# ServoShield_v2.net
KiCad netlist of a schematic drawn in EAGLE
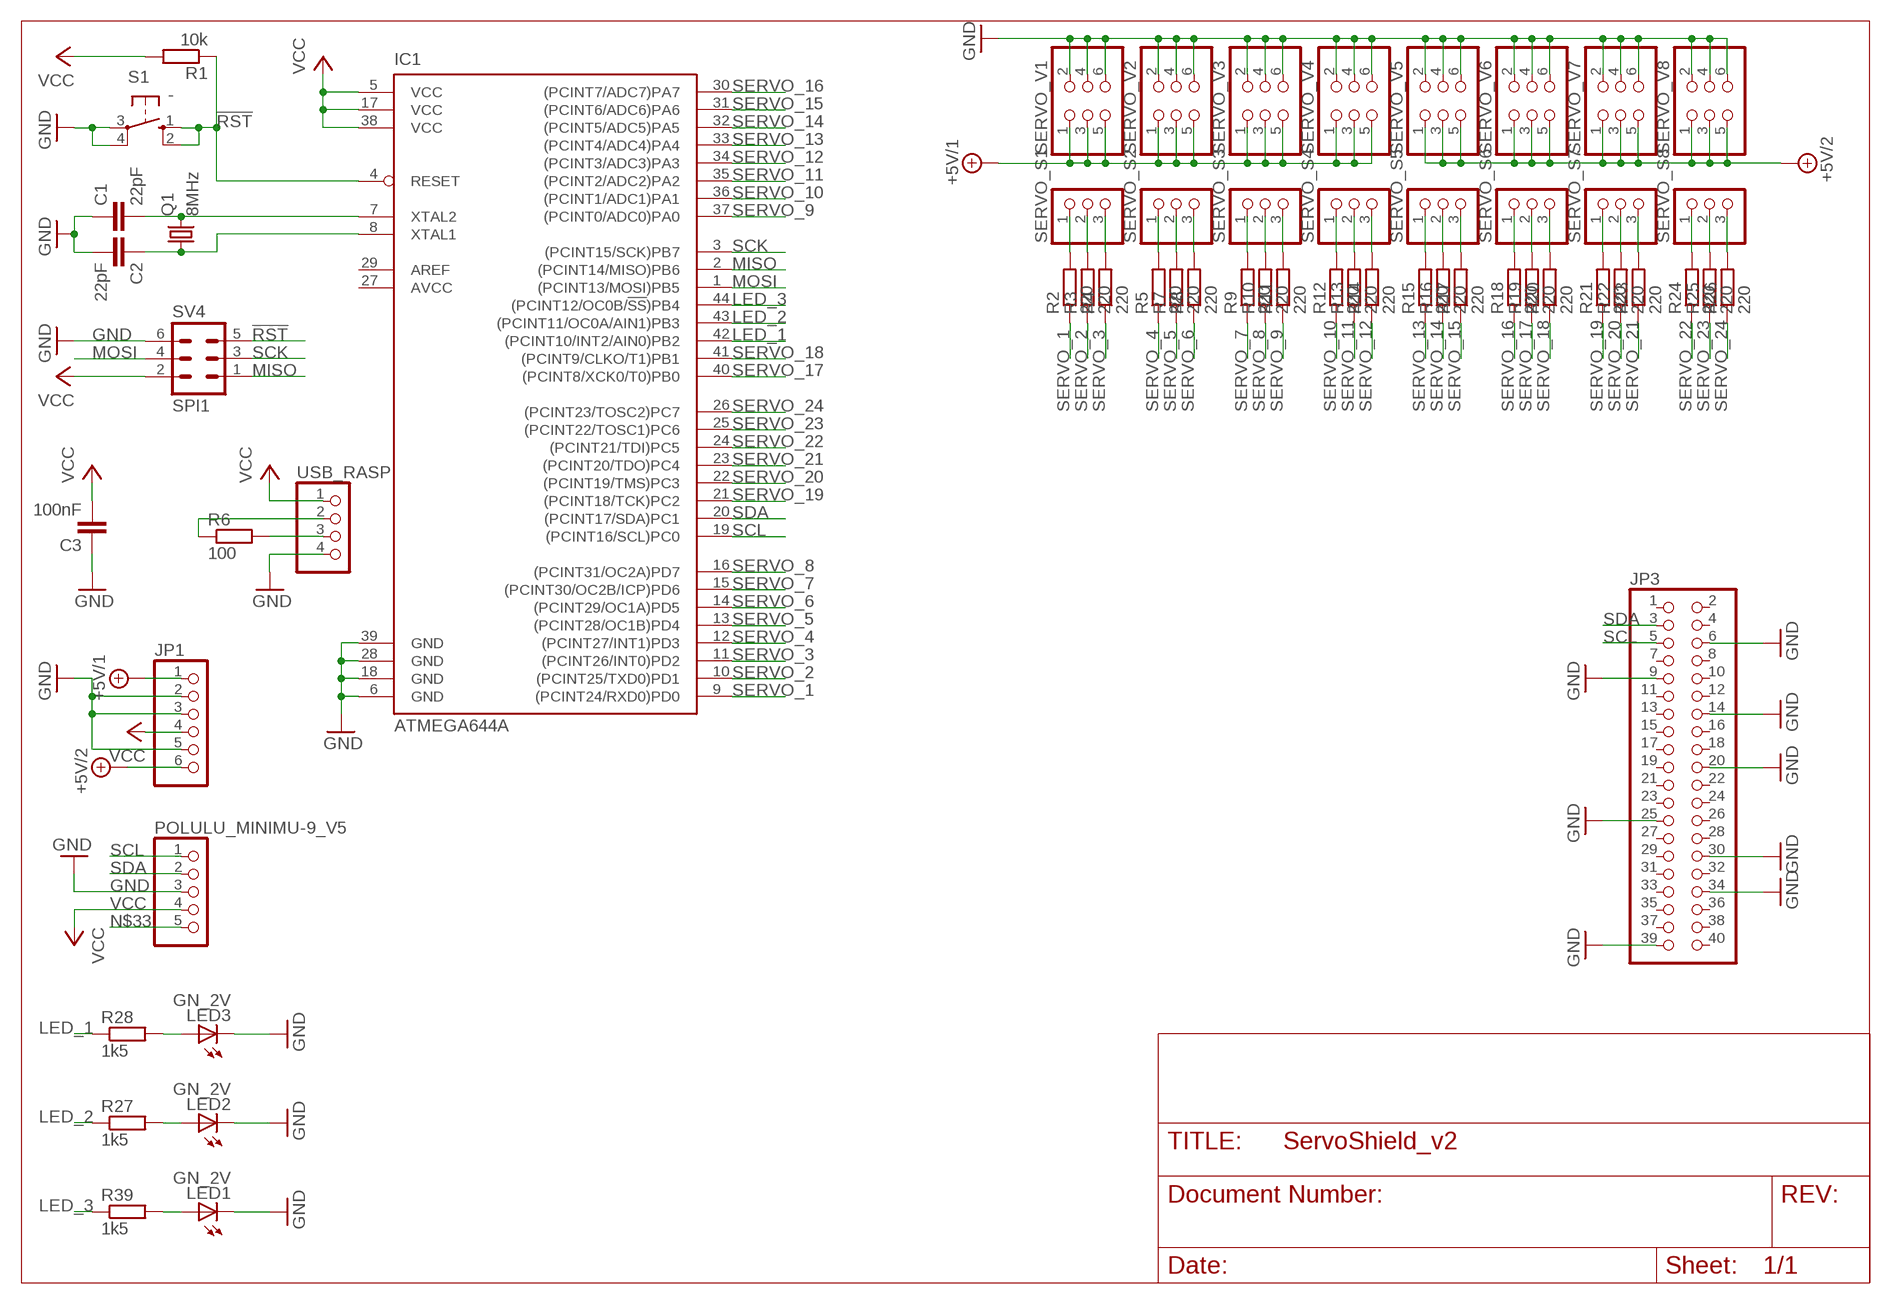
[diagram p0: schematic, sheet 1]

(export (version "E")
  (design (tool "Eeschema 10.0.6"))
  (components
    (comp (ref "C1")
      (value "22pF")
      (footprint "eagle-import:C0805")
      (libsource (lib "eagle-import") (part "C-EUC0805"))
    )
    (comp (ref "C2")
      (value "22pF")
      (footprint "eagle-import:C0805")
      (libsource (lib "eagle-import") (part "C-EUC0805"))
    )
    (comp (ref "C3")
      (value "100nF")
      (footprint "eagle-import:C0805")
      (libsource (lib "eagle-import") (part "resistor_C-EUC0805"))
    )
    (comp (ref "IC1")
      (value "ATMEGA644A")
      (footprint "eagle-import:TQFP44")
      (fields (field (name "MPN") "ATMEGA644PV-10AU"))
      (libsource (lib "eagle-import") (part "ATMEGA644A"))
    )
    (comp (ref "JP1")
      (value "PINHD-1X6")
      (footprint "eagle-import:1X06")
      (libsource (lib "eagle-import") (part "PINHD-1X6"))
    )
    (comp (ref "JP3")
      (value "PINHD-2X20")
      (footprint "eagle-import:2X20")
      (libsource (lib "eagle-import") (part "PINHD-2X20"))
    )
    (comp (ref "LED1")
      (value "GN_2V")
      (footprint "eagle-import:LED3MM")
      (libsource (lib "eagle-import") (part "LED3MM"))
    )
    (comp (ref "LED2")
      (value "GN_2V")
      (footprint "eagle-import:LED3MM")
      (libsource (lib "eagle-import") (part "LED3MM"))
    )
    (comp (ref "LED3")
      (value "GN_2V")
      (footprint "eagle-import:LED3MM")
      (libsource (lib "eagle-import") (part "LED3MM"))
    )
    (comp (ref "POLULU_MINIMU-9_V5")
      (value "PINHD-1X5")
      (footprint "eagle-import:1X05")
      (libsource (lib "eagle-import") (part "PINHD-1X5"))
    )
    (comp (ref "Q1")
      (value "8MHz")
      (footprint "eagle-import:CTS406")
      (libsource (lib "eagle-import") (part "CRYSTALCTS406"))
    )
    (comp (ref "R1")
      (value "10k")
      (footprint "eagle-import:R0805")
      (libsource (lib "eagle-import") (part "resistor_R-EU_R0805"))
    )
    (comp (ref "R2")
      (value "220")
      (footprint "eagle-import:R0805")
      (libsource (lib "eagle-import") (part "resistor_R-EU_R0805"))
    )
    (comp (ref "R3")
      (value "220")
      (footprint "eagle-import:R0805")
      (libsource (lib "eagle-import") (part "resistor_R-EU_R0805"))
    )
    (comp (ref "R4")
      (value "220")
      (footprint "eagle-import:R0805")
      (libsource (lib "eagle-import") (part "resistor_R-EU_R0805"))
    )
    (comp (ref "R5")
      (value "220")
      (footprint "eagle-import:R0805")
      (libsource (lib "eagle-import") (part "resistor_R-EU_R0805"))
    )
    (comp (ref "R6")
      (value "100")
      (footprint "eagle-import:R0805")
      (libsource (lib "eagle-import") (part "R-EU_R0805"))
    )
    (comp (ref "R7")
      (value "220")
      (footprint "eagle-import:R0805")
      (libsource (lib "eagle-import") (part "resistor_R-EU_R0805"))
    )
    (comp (ref "R8")
      (value "220")
      (footprint "eagle-import:R0805")
      (libsource (lib "eagle-import") (part "resistor_R-EU_R0805"))
    )
    (comp (ref "R9")
      (value "220")
      (footprint "eagle-import:R0805")
      (libsource (lib "eagle-import") (part "resistor_R-EU_R0805"))
    )
    (comp (ref "R10")
      (value "220")
      (footprint "eagle-import:R0805")
      (libsource (lib "eagle-import") (part "resistor_R-EU_R0805"))
    )
    (comp (ref "R11")
      (value "220")
      (footprint "eagle-import:R0805")
      (libsource (lib "eagle-import") (part "resistor_R-EU_R0805"))
    )
    (comp (ref "R12")
      (value "220")
      (footprint "eagle-import:R0805")
      (libsource (lib "eagle-import") (part "resistor_R-EU_R0805"))
    )
    (comp (ref "R13")
      (value "220")
      (footprint "eagle-import:R0805")
      (libsource (lib "eagle-import") (part "resistor_R-EU_R0805"))
    )
    (comp (ref "R14")
      (value "220")
      (footprint "eagle-import:R0805")
      (libsource (lib "eagle-import") (part "resistor_R-EU_R0805"))
    )
    (comp (ref "R15")
      (value "220")
      (footprint "eagle-import:R0805")
      (libsource (lib "eagle-import") (part "resistor_R-EU_R0805"))
    )
    (comp (ref "R16")
      (value "220")
      (footprint "eagle-import:R0805")
      (libsource (lib "eagle-import") (part "resistor_R-EU_R0805"))
    )
    (comp (ref "R17")
      (value "220")
      (footprint "eagle-import:R0805")
      (libsource (lib "eagle-import") (part "resistor_R-EU_R0805"))
    )
    (comp (ref "R18")
      (value "220")
      (footprint "eagle-import:R0805")
      (libsource (lib "eagle-import") (part "resistor_R-EU_R0805"))
    )
    (comp (ref "R19")
      (value "220")
      (footprint "eagle-import:R0805")
      (libsource (lib "eagle-import") (part "resistor_R-EU_R0805"))
    )
    (comp (ref "R20")
      (value "220")
      (footprint "eagle-import:R0805")
      (libsource (lib "eagle-import") (part "resistor_R-EU_R0805"))
    )
    (comp (ref "R21")
      (value "220")
      (footprint "eagle-import:R0805")
      (libsource (lib "eagle-import") (part "resistor_R-EU_R0805"))
    )
    (comp (ref "R22")
      (value "220")
      (footprint "eagle-import:R0805")
      (libsource (lib "eagle-import") (part "resistor_R-EU_R0805"))
    )
    (comp (ref "R23")
      (value "220")
      (footprint "eagle-import:R0805")
      (libsource (lib "eagle-import") (part "resistor_R-EU_R0805"))
    )
    (comp (ref "R24")
      (value "220")
      (footprint "eagle-import:R0805")
      (libsource (lib "eagle-import") (part "resistor_R-EU_R0805"))
    )
    (comp (ref "R25")
      (value "220")
      (footprint "eagle-import:R0805")
      (libsource (lib "eagle-import") (part "resistor_R-EU_R0805"))
    )
    (comp (ref "R26")
      (value "220")
      (footprint "eagle-import:R0805")
      (libsource (lib "eagle-import") (part "resistor_R-EU_R0805"))
    )
    (comp (ref "R27")
      (value "1k5")
      (footprint "eagle-import:R0805")
      (libsource (lib "eagle-import") (part "R-EU_R0805"))
    )
    (comp (ref "R28")
      (value "1k5")
      (footprint "eagle-import:R0805")
      (libsource (lib "eagle-import") (part "R-EU_R0805"))
    )
    (comp (ref "R39")
      (value "1k5")
      (footprint "eagle-import:R0805")
      (libsource (lib "eagle-import") (part "R-EU_R0805"))
    )
    (comp (ref "S1")
      (value "-")
      (footprint "eagle-import:B3F-10XX")
      (fields (field (name "MPN") "B3F-1000"))
      (libsource (lib "eagle-import") (part "10-XX"))
    )
    (comp (ref "SERVO_S1")
      (value "PINHD-1X3")
      (footprint "eagle-import:1X03")
      (libsource (lib "eagle-import") (part "PINHD-1X3"))
    )
    (comp (ref "SERVO_S2")
      (value "PINHD-1X3")
      (footprint "eagle-import:1X03")
      (libsource (lib "eagle-import") (part "PINHD-1X3"))
    )
    (comp (ref "SERVO_S3")
      (value "PINHD-1X3")
      (footprint "eagle-import:1X03")
      (libsource (lib "eagle-import") (part "PINHD-1X3"))
    )
    (comp (ref "SERVO_S4")
      (value "PINHD-1X3")
      (footprint "eagle-import:1X03")
      (libsource (lib "eagle-import") (part "PINHD-1X3"))
    )
    (comp (ref "SERVO_S5")
      (value "PINHD-1X3")
      (footprint "eagle-import:1X03")
      (libsource (lib "eagle-import") (part "PINHD-1X3"))
    )
    (comp (ref "SERVO_S6")
      (value "PINHD-1X3")
      (footprint "eagle-import:1X03")
      (libsource (lib "eagle-import") (part "PINHD-1X3"))
    )
    (comp (ref "SERVO_S7")
      (value "PINHD-1X3")
      (footprint "eagle-import:1X03")
      (libsource (lib "eagle-import") (part "PINHD-1X3"))
    )
    (comp (ref "SERVO_S8")
      (value "PINHD-1X3")
      (footprint "eagle-import:1X03")
      (libsource (lib "eagle-import") (part "PINHD-1X3"))
    )
    (comp (ref "SERVO_V1")
      (value "PINHD-2X3")
      (footprint "eagle-import:2X03")
      (libsource (lib "eagle-import") (part "PINHD-2X3"))
    )
    (comp (ref "SERVO_V2")
      (value "PINHD-2X3")
      (footprint "eagle-import:2X03")
      (libsource (lib "eagle-import") (part "PINHD-2X3"))
    )
    (comp (ref "SERVO_V3")
      (value "PINHD-2X3")
      (footprint "eagle-import:2X03")
      (libsource (lib "eagle-import") (part "PINHD-2X3"))
    )
    (comp (ref "SERVO_V4")
      (value "PINHD-2X3")
      (footprint "eagle-import:2X03")
      (libsource (lib "eagle-import") (part "PINHD-2X3"))
    )
    (comp (ref "SERVO_V5")
      (value "PINHD-2X3")
      (footprint "eagle-import:2X03")
      (libsource (lib "eagle-import") (part "PINHD-2X3"))
    )
    (comp (ref "SERVO_V6")
      (value "PINHD-2X3")
      (footprint "eagle-import:2X03")
      (libsource (lib "eagle-import") (part "PINHD-2X3"))
    )
    (comp (ref "SERVO_V7")
      (value "PINHD-2X3")
      (footprint "eagle-import:2X03")
      (libsource (lib "eagle-import") (part "PINHD-2X3"))
    )
    (comp (ref "SERVO_V8")
      (value "PINHD-2X3")
      (footprint "eagle-import:2X03")
      (libsource (lib "eagle-import") (part "PINHD-2X3"))
    )
    (comp (ref "SV4")
      (value "SPI1")
      (footprint "eagle-import:ML6")
      (libsource (lib "eagle-import") (part "ML6"))
    )
    (comp (ref "USB_RASP")
      (value "PINHD-1X4")
      (footprint "eagle-import:1X04")
      (libsource (lib "eagle-import") (part "PINHD-1X4"))
    )
  )
  (nets
    (net (code "1") (name "+5V{slash}1") (class "Default")
      (node (ref "JP1") (pin "1") (pinfunction "1_1") (pintype "passive"))
      (node (ref "SERVO_V1") (pin "1") (pinfunction "1_1") (pintype "passive"))
      (node (ref "SERVO_V1") (pin "3") (pinfunction "3_3") (pintype "passive"))
      (node (ref "SERVO_V1") (pin "5") (pinfunction "5_5") (pintype "passive"))
      (node (ref "SERVO_V2") (pin "1") (pinfunction "1_1") (pintype "passive"))
      (node (ref "SERVO_V2") (pin "3") (pinfunction "3_3") (pintype "passive"))
      (node (ref "SERVO_V2") (pin "5") (pinfunction "5_5") (pintype "passive"))
      (node (ref "SERVO_V3") (pin "1") (pinfunction "1_1") (pintype "passive"))
      (node (ref "SERVO_V3") (pin "3") (pinfunction "3_3") (pintype "passive"))
      (node (ref "SERVO_V3") (pin "5") (pinfunction "5_5") (pintype "passive"))
      (node (ref "SERVO_V4") (pin "1") (pinfunction "1_1") (pintype "passive"))
      (node (ref "SERVO_V4") (pin "3") (pinfunction "3_3") (pintype "passive"))
      (node (ref "SERVO_V4") (pin "5") (pinfunction "5_5") (pintype "passive"))
    )
    (net (code "2") (name "+5V{slash}2") (class "Default")
      (node (ref "JP1") (pin "6") (pinfunction "6_6") (pintype "passive"))
      (node (ref "SERVO_V5") (pin "1") (pinfunction "1_1") (pintype "passive"))
      (node (ref "SERVO_V5") (pin "3") (pinfunction "3_3") (pintype "passive"))
      (node (ref "SERVO_V5") (pin "5") (pinfunction "5_5") (pintype "passive"))
      (node (ref "SERVO_V6") (pin "1") (pinfunction "1_1") (pintype "passive"))
      (node (ref "SERVO_V6") (pin "3") (pinfunction "3_3") (pintype "passive"))
      (node (ref "SERVO_V6") (pin "5") (pinfunction "5_5") (pintype "passive"))
      (node (ref "SERVO_V7") (pin "1") (pinfunction "1_1") (pintype "passive"))
      (node (ref "SERVO_V7") (pin "3") (pinfunction "3_3") (pintype "passive"))
      (node (ref "SERVO_V7") (pin "5") (pinfunction "5_5") (pintype "passive"))
      (node (ref "SERVO_V8") (pin "1") (pinfunction "1_1") (pintype "passive"))
      (node (ref "SERVO_V8") (pin "3") (pinfunction "3_3") (pintype "passive"))
      (node (ref "SERVO_V8") (pin "5") (pinfunction "5_5") (pintype "passive"))
    )
    (net (code "3") (name "/AVCC") (class "Default")
      (node (ref "IC1") (pin "27") (pinfunction "AVCC_27") (pintype "power_in"))
    )
    (net (code "4") (name "/LED_1") (class "Default")
      (node (ref "IC1") (pin "42") (pinfunction "(PCINT10/INT2/AIN0)PB2_42") (pintype "bidirectional"))
      (node (ref "R28") (pin "1") (pinfunction "1_1") (pintype "passive"))
    )
    (net (code "5") (name "/LED_2") (class "Default")
      (node (ref "IC1") (pin "43") (pinfunction "(PCINT11/OC0A/AIN1)PB3_43") (pintype "bidirectional"))
      (node (ref "R27") (pin "1") (pinfunction "1_1") (pintype "passive"))
    )
    (net (code "6") (name "/LED_3") (class "Default")
      (node (ref "IC1") (pin "44") (pinfunction "(PCINT12/OC0B/~{SS})PB4_44") (pintype "bidirectional"))
      (node (ref "R39") (pin "1") (pinfunction "1_1") (pintype "passive"))
    )
    (net (code "7") (name "/MISO") (class "Default")
      (node (ref "IC1") (pin "2") (pinfunction "(PCINT14/MISO)PB6_2") (pintype "bidirectional"))
      (node (ref "SV4") (pin "1") (pinfunction "1_1") (pintype "passive"))
    )
    (net (code "8") (name "/MOSI") (class "Default")
      (node (ref "IC1") (pin "1") (pinfunction "(PCINT13/MOSI)PB5_1") (pintype "bidirectional"))
      (node (ref "SV4") (pin "4") (pinfunction "4_4") (pintype "passive"))
    )
    (net (code "9") (name "/N$33") (class "Default")
      (node (ref "POLULU_MINIMU-9_V5") (pin "5") (pinfunction "5_5") (pintype "passive"))
    )
    (net (code "10") (name "/SCK") (class "Default")
      (node (ref "IC1") (pin "3") (pinfunction "(PCINT15/SCK)PB7_3") (pintype "bidirectional"))
      (node (ref "SV4") (pin "3") (pinfunction "3_3") (pintype "passive"))
    )
    (net (code "11") (name "/SCL") (class "Default")
      (node (ref "IC1") (pin "19") (pinfunction "(PCINT16/SCL)PC0_19") (pintype "output"))
      (node (ref "JP3") (pin "5") (pinfunction "5_5") (pintype "passive"))
      (node (ref "POLULU_MINIMU-9_V5") (pin "1") (pinfunction "1_1") (pintype "passive"))
    )
    (net (code "12") (name "/SDA") (class "Default")
      (node (ref "IC1") (pin "20") (pinfunction "(PCINT17/SDA)PC1_20") (pintype "output"))
      (node (ref "JP3") (pin "3") (pinfunction "3_3") (pintype "passive"))
      (node (ref "POLULU_MINIMU-9_V5") (pin "2") (pinfunction "2_2") (pintype "passive"))
    )
    (net (code "13") (name "/SERVO_1") (class "Default")
      (node (ref "IC1") (pin "9") (pinfunction "(PCINT24/RXD0)PD0_9") (pintype "bidirectional"))
      (node (ref "R2") (pin "1") (pinfunction "1_1") (pintype "passive"))
    )
    (net (code "14") (name "/SERVO_2") (class "Default")
      (node (ref "IC1") (pin "10") (pinfunction "(PCINT25/TXD0)PD1_10") (pintype "bidirectional"))
      (node (ref "R3") (pin "1") (pinfunction "1_1") (pintype "passive"))
    )
    (net (code "15") (name "/SERVO_3") (class "Default")
      (node (ref "IC1") (pin "11") (pinfunction "(PCINT26/INT0)PD2_11") (pintype "bidirectional"))
      (node (ref "R4") (pin "1") (pinfunction "1_1") (pintype "passive"))
    )
    (net (code "16") (name "/SERVO_4") (class "Default")
      (node (ref "IC1") (pin "12") (pinfunction "(PCINT27/INT1)PD3_12") (pintype "bidirectional"))
      (node (ref "R5") (pin "1") (pinfunction "1_1") (pintype "passive"))
    )
    (net (code "17") (name "/SERVO_5") (class "Default")
      (node (ref "IC1") (pin "13") (pinfunction "(PCINT28/OC1B)PD4_13") (pintype "bidirectional"))
      (node (ref "R7") (pin "1") (pinfunction "1_1") (pintype "passive"))
    )
    (net (code "18") (name "/SERVO_6") (class "Default")
      (node (ref "IC1") (pin "14") (pinfunction "(PCINT29/OC1A)PD5_14") (pintype "bidirectional"))
      (node (ref "R8") (pin "1") (pinfunction "1_1") (pintype "passive"))
    )
    (net (code "19") (name "/SERVO_7") (class "Default")
      (node (ref "IC1") (pin "15") (pinfunction "(PCINT30/OC2B/ICP)PD6_15") (pintype "bidirectional"))
      (node (ref "R9") (pin "1") (pinfunction "1_1") (pintype "passive"))
    )
    (net (code "20") (name "/SERVO_8") (class "Default")
      (node (ref "IC1") (pin "16") (pinfunction "(PCINT31/OC2A)PD7_16") (pintype "bidirectional"))
      (node (ref "R10") (pin "1") (pinfunction "1_1") (pintype "passive"))
    )
    (net (code "21") (name "/SERVO_9") (class "Default")
      (node (ref "IC1") (pin "37") (pinfunction "(PCINT0/ADC0)PA0_37") (pintype "bidirectional"))
      (node (ref "R11") (pin "1") (pinfunction "1_1") (pintype "passive"))
    )
    (net (code "22") (name "/SERVO_10") (class "Default")
      (node (ref "IC1") (pin "36") (pinfunction "(PCINT1/ADC1)PA1_36") (pintype "bidirectional"))
      (node (ref "R12") (pin "1") (pinfunction "1_1") (pintype "passive"))
    )
    (net (code "23") (name "/SERVO_11") (class "Default")
      (node (ref "IC1") (pin "35") (pinfunction "(PCINT2/ADC2)PA2_35") (pintype "bidirectional"))
      (node (ref "R13") (pin "1") (pinfunction "1_1") (pintype "passive"))
    )
    (net (code "24") (name "/SERVO_12") (class "Default")
      (node (ref "IC1") (pin "34") (pinfunction "(PCINT3/ADC3)PA3_34") (pintype "bidirectional"))
      (node (ref "R14") (pin "1") (pinfunction "1_1") (pintype "passive"))
    )
    (net (code "25") (name "/SERVO_13") (class "Default")
      (node (ref "IC1") (pin "33") (pinfunction "(PCINT4/ADC4)PA4_33") (pintype "bidirectional"))
      (node (ref "R15") (pin "1") (pinfunction "1_1") (pintype "passive"))
    )
    (net (code "26") (name "/SERVO_14") (class "Default")
      (node (ref "IC1") (pin "32") (pinfunction "(PCINT5/ADC5)PA5_32") (pintype "bidirectional"))
      (node (ref "R16") (pin "1") (pinfunction "1_1") (pintype "passive"))
    )
    (net (code "27") (name "/SERVO_15") (class "Default")
      (node (ref "IC1") (pin "31") (pinfunction "(PCINT6/ADC6)PA6_31") (pintype "bidirectional"))
      (node (ref "R17") (pin "1") (pinfunction "1_1") (pintype "passive"))
    )
    (net (code "28") (name "/SERVO_16") (class "Default")
      (node (ref "IC1") (pin "30") (pinfunction "(PCINT7/ADC7)PA7_30") (pintype "bidirectional"))
      (node (ref "R18") (pin "1") (pinfunction "1_1") (pintype "passive"))
    )
    (net (code "29") (name "/SERVO_17") (class "Default")
      (node (ref "IC1") (pin "40") (pinfunction "(PCINT8/XCK0/T0)PB0_40") (pintype "bidirectional"))
      (node (ref "R19") (pin "1") (pinfunction "1_1") (pintype "passive"))
    )
    (net (code "30") (name "/SERVO_18") (class "Default")
      (node (ref "IC1") (pin "41") (pinfunction "(PCINT9/CLKO/T1)PB1_41") (pintype "bidirectional"))
      (node (ref "R20") (pin "1") (pinfunction "1_1") (pintype "passive"))
    )
    (net (code "31") (name "/SERVO_19") (class "Default")
      (node (ref "IC1") (pin "21") (pinfunction "(PCINT18/TCK)PC2_21") (pintype "output"))
      (node (ref "R21") (pin "1") (pinfunction "1_1") (pintype "passive"))
    )
    (net (code "32") (name "/SERVO_20") (class "Default")
      (node (ref "IC1") (pin "22") (pinfunction "(PCINT19/TMS)PC3_22") (pintype "output"))
      (node (ref "R22") (pin "1") (pinfunction "1_1") (pintype "passive"))
    )
    (net (code "33") (name "/SERVO_21") (class "Default")
      (node (ref "IC1") (pin "23") (pinfunction "(PCINT20/TDO)PC4_23") (pintype "output"))
      (node (ref "R23") (pin "1") (pinfunction "1_1") (pintype "passive"))
    )
    (net (code "34") (name "/SERVO_22") (class "Default")
      (node (ref "IC1") (pin "24") (pinfunction "(PCINT21/TDI)PC5_24") (pintype "output"))
      (node (ref "R24") (pin "1") (pinfunction "1_1") (pintype "passive"))
    )
    (net (code "35") (name "/SERVO_23") (class "Default")
      (node (ref "IC1") (pin "25") (pinfunction "(PCINT22/TOSC1)PC6_25") (pintype "output"))
      (node (ref "R25") (pin "1") (pinfunction "1_1") (pintype "passive"))
    )
    (net (code "36") (name "/SERVO_24") (class "Default")
      (node (ref "IC1") (pin "26") (pinfunction "(PCINT23/TOSC2)PC7_26") (pintype "output"))
      (node (ref "R26") (pin "1") (pinfunction "1_1") (pintype "passive"))
    )
    (net (code "37") (name "/~{RST}") (class "Default")
      (node (ref "IC1") (pin "4") (pinfunction "RESET_4") (pintype "input"))
      (node (ref "R1") (pin "1") (pinfunction "1_1") (pintype "passive"))
      (node (ref "S1") (pin "1") (pinfunction "S_1") (pintype "passive"))
      (node (ref "S1") (pin "2") (pinfunction "S1_2") (pintype "passive"))
      (node (ref "SV4") (pin "5") (pinfunction "5_5") (pintype "passive"))
    )
    (net (code "38") (name "GND") (class "Default")
      (node (ref "C1") (pin "1") (pinfunction "1_1") (pintype "passive"))
      (node (ref "C2") (pin "2") (pinfunction "2_2") (pintype "passive"))
      (node (ref "C3") (pin "1") (pinfunction "1_1") (pintype "passive"))
      (node (ref "IC1") (pin "18") (pinfunction "GND_18") (pintype "power_in"))
      (node (ref "IC1") (pin "28") (pinfunction "GND_28") (pintype "power_in"))
      (node (ref "IC1") (pin "39") (pinfunction "GND_39") (pintype "power_in"))
      (node (ref "IC1") (pin "6") (pinfunction "GND_6") (pintype "power_in"))
      (node (ref "JP1") (pin "2") (pinfunction "2_2") (pintype "passive"))
      (node (ref "JP1") (pin "3") (pinfunction "3_3") (pintype "passive"))
      (node (ref "JP1") (pin "5") (pinfunction "5_5") (pintype "passive"))
      (node (ref "JP3") (pin "14") (pinfunction "14_14") (pintype "passive"))
      (node (ref "JP3") (pin "20") (pinfunction "20_20") (pintype "passive"))
      (node (ref "JP3") (pin "25") (pinfunction "25_25") (pintype "passive"))
      (node (ref "JP3") (pin "30") (pinfunction "30_30") (pintype "passive"))
      (node (ref "JP3") (pin "34") (pinfunction "34_34") (pintype "passive"))
      (node (ref "JP3") (pin "39") (pinfunction "39_39") (pintype "passive"))
      (node (ref "JP3") (pin "6") (pinfunction "6_6") (pintype "passive"))
      (node (ref "JP3") (pin "9") (pinfunction "9_9") (pintype "passive"))
      (node (ref "LED1") (pin "K") (pinfunction "C_K") (pintype "passive"))
      (node (ref "LED2") (pin "K") (pinfunction "C_K") (pintype "passive"))
      (node (ref "LED3") (pin "K") (pinfunction "C_K") (pintype "passive"))
      (node (ref "POLULU_MINIMU-9_V5") (pin "3") (pinfunction "3_3") (pintype "passive"))
      (node (ref "S1") (pin "3") (pinfunction "P_3") (pintype "passive"))
      (node (ref "S1") (pin "4") (pinfunction "P1_4") (pintype "passive"))
      (node (ref "SERVO_V1") (pin "2") (pinfunction "2_2") (pintype "passive"))
      (node (ref "SERVO_V1") (pin "4") (pinfunction "4_4") (pintype "passive"))
      (node (ref "SERVO_V1") (pin "6") (pinfunction "6_6") (pintype "passive"))
      (node (ref "SERVO_V2") (pin "2") (pinfunction "2_2") (pintype "passive"))
      (node (ref "SERVO_V2") (pin "4") (pinfunction "4_4") (pintype "passive"))
      (node (ref "SERVO_V2") (pin "6") (pinfunction "6_6") (pintype "passive"))
      (node (ref "SERVO_V3") (pin "2") (pinfunction "2_2") (pintype "passive"))
      (node (ref "SERVO_V3") (pin "4") (pinfunction "4_4") (pintype "passive"))
      (node (ref "SERVO_V3") (pin "6") (pinfunction "6_6") (pintype "passive"))
      (node (ref "SERVO_V4") (pin "2") (pinfunction "2_2") (pintype "passive"))
      (node (ref "SERVO_V4") (pin "4") (pinfunction "4_4") (pintype "passive"))
      (node (ref "SERVO_V4") (pin "6") (pinfunction "6_6") (pintype "passive"))
      (node (ref "SERVO_V5") (pin "2") (pinfunction "2_2") (pintype "passive"))
      (node (ref "SERVO_V5") (pin "4") (pinfunction "4_4") (pintype "passive"))
      (node (ref "SERVO_V5") (pin "6") (pinfunction "6_6") (pintype "passive"))
      (node (ref "SERVO_V6") (pin "2") (pinfunction "2_2") (pintype "passive"))
      (node (ref "SERVO_V6") (pin "4") (pinfunction "4_4") (pintype "passive"))
      (node (ref "SERVO_V6") (pin "6") (pinfunction "6_6") (pintype "passive"))
      (node (ref "SERVO_V7") (pin "2") (pinfunction "2_2") (pintype "passive"))
      (node (ref "SERVO_V7") (pin "4") (pinfunction "4_4") (pintype "passive"))
      (node (ref "SERVO_V7") (pin "6") (pinfunction "6_6") (pintype "passive"))
      (node (ref "SERVO_V8") (pin "2") (pinfunction "2_2") (pintype "passive"))
      (node (ref "SERVO_V8") (pin "4") (pinfunction "4_4") (pintype "passive"))
      (node (ref "SERVO_V8") (pin "6") (pinfunction "6_6") (pintype "passive"))
      (node (ref "SV4") (pin "6") (pinfunction "6_6") (pintype "passive"))
      (node (ref "USB_RASP") (pin "4") (pinfunction "4_4") (pintype "passive"))
    )
    (net (code "39") (name "Net-(IC1-XTAL1)") (class "Default")
      (node (ref "C2") (pin "1") (pinfunction "1_1") (pintype "passive"))
      (node (ref "IC1") (pin "8") (pinfunction "XTAL1_8") (pintype "bidirectional"))
      (node (ref "Q1") (pin "1") (pinfunction "1_1") (pintype "passive"))
    )
    (net (code "40") (name "Net-(IC1-XTAL2)") (class "Default")
      (node (ref "C1") (pin "2") (pinfunction "2_2") (pintype "passive"))
      (node (ref "IC1") (pin "7") (pinfunction "XTAL2_7") (pintype "bidirectional"))
      (node (ref "Q1") (pin "3") (pinfunction "2_3") (pintype "passive"))
    )
    (net (code "41") (name "Net-(LED1-PadA)") (class "Default")
      (node (ref "LED1") (pin "A") (pinfunction "A_A") (pintype "passive"))
      (node (ref "R39") (pin "2") (pinfunction "2_2") (pintype "passive"))
    )
    (net (code "42") (name "Net-(LED2-PadA)") (class "Default")
      (node (ref "LED2") (pin "A") (pinfunction "A_A") (pintype "passive"))
      (node (ref "R27") (pin "2") (pinfunction "2_2") (pintype "passive"))
    )
    (net (code "43") (name "Net-(LED3-PadA)") (class "Default")
      (node (ref "LED3") (pin "A") (pinfunction "A_A") (pintype "passive"))
      (node (ref "R28") (pin "2") (pinfunction "2_2") (pintype "passive"))
    )
    (net (code "44") (name "Net-(R2-Pad2)") (class "Default")
      (node (ref "R2") (pin "2") (pinfunction "2_2") (pintype "passive"))
      (node (ref "SERVO_S1") (pin "1") (pinfunction "1_1") (pintype "passive"))
    )
    (net (code "45") (name "Net-(R3-Pad2)") (class "Default")
      (node (ref "R3") (pin "2") (pinfunction "2_2") (pintype "passive"))
      (node (ref "SERVO_S1") (pin "2") (pinfunction "2_2") (pintype "passive"))
    )
    (net (code "46") (name "Net-(R4-Pad2)") (class "Default")
      (node (ref "R4") (pin "2") (pinfunction "2_2") (pintype "passive"))
      (node (ref "SERVO_S1") (pin "3") (pinfunction "3_3") (pintype "passive"))
    )
    (net (code "47") (name "Net-(R5-Pad2)") (class "Default")
      (node (ref "R5") (pin "2") (pinfunction "2_2") (pintype "passive"))
      (node (ref "SERVO_S2") (pin "1") (pinfunction "1_1") (pintype "passive"))
    )
    (net (code "48") (name "Net-(R6-Pad1)") (class "Default")
      (node (ref "R6") (pin "1") (pinfunction "1_1") (pintype "passive"))
      (node (ref "USB_RASP") (pin "2") (pinfunction "2_2") (pintype "passive"))
    )
    (net (code "49") (name "Net-(R6-Pad2)") (class "Default")
      (node (ref "R6") (pin "2") (pinfunction "2_2") (pintype "passive"))
      (node (ref "USB_RASP") (pin "3") (pinfunction "3_3") (pintype "passive"))
    )
    (net (code "50") (name "Net-(R7-Pad2)") (class "Default")
      (node (ref "R7") (pin "2") (pinfunction "2_2") (pintype "passive"))
      (node (ref "SERVO_S2") (pin "2") (pinfunction "2_2") (pintype "passive"))
    )
    (net (code "51") (name "Net-(R8-Pad2)") (class "Default")
      (node (ref "R8") (pin "2") (pinfunction "2_2") (pintype "passive"))
      (node (ref "SERVO_S2") (pin "3") (pinfunction "3_3") (pintype "passive"))
    )
    (net (code "52") (name "Net-(R9-Pad2)") (class "Default")
      (node (ref "R9") (pin "2") (pinfunction "2_2") (pintype "passive"))
      (node (ref "SERVO_S3") (pin "1") (pinfunction "1_1") (pintype "passive"))
    )
    (net (code "53") (name "Net-(R10-Pad2)") (class "Default")
      (node (ref "R10") (pin "2") (pinfunction "2_2") (pintype "passive"))
      (node (ref "SERVO_S3") (pin "2") (pinfunction "2_2") (pintype "passive"))
    )
    (net (code "54") (name "Net-(R11-Pad2)") (class "Default")
      (node (ref "R11") (pin "2") (pinfunction "2_2") (pintype "passive"))
      (node (ref "SERVO_S3") (pin "3") (pinfunction "3_3") (pintype "passive"))
    )
    (net (code "55") (name "Net-(R12-Pad2)") (class "Default")
      (node (ref "R12") (pin "2") (pinfunction "2_2") (pintype "passive"))
      (node (ref "SERVO_S4") (pin "1") (pinfunction "1_1") (pintype "passive"))
    )
    (net (code "56") (name "Net-(R13-Pad2)") (class "Default")
      (node (ref "R13") (pin "2") (pinfunction "2_2") (pintype "passive"))
      (node (ref "SERVO_S4") (pin "2") (pinfunction "2_2") (pintype "passive"))
    )
    (net (code "57") (name "Net-(R14-Pad2)") (class "Default")
      (node (ref "R14") (pin "2") (pinfunction "2_2") (pintype "passive"))
      (node (ref "SERVO_S4") (pin "3") (pinfunction "3_3") (pintype "passive"))
    )
    (net (code "58") (name "Net-(R15-Pad2)") (class "Default")
      (node (ref "R15") (pin "2") (pinfunction "2_2") (pintype "passive"))
      (node (ref "SERVO_S5") (pin "1") (pinfunction "1_1") (pintype "passive"))
    )
    (net (code "59") (name "Net-(R16-Pad2)") (class "Default")
      (node (ref "R16") (pin "2") (pinfunction "2_2") (pintype "passive"))
      (node (ref "SERVO_S5") (pin "2") (pinfunction "2_2") (pintype "passive"))
    )
    (net (code "60") (name "Net-(R17-Pad2)") (class "Default")
      (node (ref "R17") (pin "2") (pinfunction "2_2") (pintype "passive"))
      (node (ref "SERVO_S5") (pin "3") (pinfunction "3_3") (pintype "passive"))
    )
    (net (code "61") (name "Net-(R18-Pad2)") (class "Default")
      (node (ref "R18") (pin "2") (pinfunction "2_2") (pintype "passive"))
      (node (ref "SERVO_S6") (pin "1") (pinfunction "1_1") (pintype "passive"))
    )
    (net (code "62") (name "Net-(R19-Pad2)") (class "Default")
      (node (ref "R19") (pin "2") (pinfunction "2_2") (pintype "passive"))
      (node (ref "SERVO_S6") (pin "2") (pinfunction "2_2") (pintype "passive"))
    )
    (net (code "63") (name "Net-(R20-Pad2)") (class "Default")
      (node (ref "R20") (pin "2") (pinfunction "2_2") (pintype "passive"))
      (node (ref "SERVO_S6") (pin "3") (pinfunction "3_3") (pintype "passive"))
    )
    (net (code "64") (name "Net-(R21-Pad2)") (class "Default")
      (node (ref "R21") (pin "2") (pinfunction "2_2") (pintype "passive"))
      (node (ref "SERVO_S7") (pin "1") (pinfunction "1_1") (pintype "passive"))
    )
    (net (code "65") (name "Net-(R22-Pad2)") (class "Default")
      (node (ref "R22") (pin "2") (pinfunction "2_2") (pintype "passive"))
      (node (ref "SERVO_S7") (pin "2") (pinfunction "2_2") (pintype "passive"))
    )
    (net (code "66") (name "Net-(R23-Pad2)") (class "Default")
      (node (ref "R23") (pin "2") (pinfunction "2_2") (pintype "passive"))
      (node (ref "SERVO_S7") (pin "3") (pinfunction "3_3") (pintype "passive"))
    )
    (net (code "67") (name "Net-(R24-Pad2)") (class "Default")
      (node (ref "R24") (pin "2") (pinfunction "2_2") (pintype "passive"))
      (node (ref "SERVO_S8") (pin "1") (pinfunction "1_1") (pintype "passive"))
    )
    (net (code "68") (name "Net-(R25-Pad2)") (class "Default")
      (node (ref "R25") (pin "2") (pinfunction "2_2") (pintype "passive"))
      (node (ref "SERVO_S8") (pin "2") (pinfunction "2_2") (pintype "passive"))
    )
    (net (code "69") (name "Net-(R26-Pad2)") (class "Default")
      (node (ref "R26") (pin "2") (pinfunction "2_2") (pintype "passive"))
      (node (ref "SERVO_S8") (pin "3") (pinfunction "3_3") (pintype "passive"))
    )
    (net (code "70") (name "VCC") (class "Default")
      (node (ref "C3") (pin "2") (pinfunction "2_2") (pintype "passive"))
      (node (ref "IC1") (pin "17") (pinfunction "VCC_17") (pintype "power_in"))
      (node (ref "IC1") (pin "38") (pinfunction "VCC_38") (pintype "power_in"))
      (node (ref "IC1") (pin "5") (pinfunction "VCC_5") (pintype "power_in"))
      (node (ref "JP1") (pin "4") (pinfunction "4_4") (pintype "passive"))
      (node (ref "POLULU_MINIMU-9_V5") (pin "4") (pinfunction "4_4") (pintype "passive"))
      (node (ref "R1") (pin "2") (pinfunction "2_2") (pintype "passive"))
      (node (ref "SV4") (pin "2") (pinfunction "2_2") (pintype "passive"))
      (node (ref "USB_RASP") (pin "1") (pinfunction "1_1") (pintype "passive"))
    )
    (net (code "71") (name "unconnected-(IC1-AREF-Pad29)") (class "Default")
      (node (ref "IC1") (pin "29") (pinfunction "AREF_29") (pintype "passive"))
    )
    (net (code "72") (name "unconnected-(JP3-Pad1)") (class "Default")
      (node (ref "JP3") (pin "1") (pinfunction "1_1") (pintype "passive"))
    )
    (net (code "73") (name "unconnected-(JP3-Pad2)") (class "Default")
      (node (ref "JP3") (pin "2") (pinfunction "2_2") (pintype "passive"))
    )
    (net (code "74") (name "unconnected-(JP3-Pad4)") (class "Default")
      (node (ref "JP3") (pin "4") (pinfunction "4_4") (pintype "passive"))
    )
    (net (code "75") (name "unconnected-(JP3-Pad7)") (class "Default")
      (node (ref "JP3") (pin "7") (pinfunction "7_7") (pintype "passive"))
    )
    (net (code "76") (name "unconnected-(JP3-Pad8)") (class "Default")
      (node (ref "JP3") (pin "8") (pinfunction "8_8") (pintype "passive"))
    )
    (net (code "77") (name "unconnected-(JP3-Pad10)") (class "Default")
      (node (ref "JP3") (pin "10") (pinfunction "10_10") (pintype "passive"))
    )
    (net (code "78") (name "unconnected-(JP3-Pad11)") (class "Default")
      (node (ref "JP3") (pin "11") (pinfunction "11_11") (pintype "passive"))
    )
    (net (code "79") (name "unconnected-(JP3-Pad12)") (class "Default")
      (node (ref "JP3") (pin "12") (pinfunction "12_12") (pintype "passive"))
    )
    (net (code "80") (name "unconnected-(JP3-Pad13)") (class "Default")
      (node (ref "JP3") (pin "13") (pinfunction "13_13") (pintype "passive"))
    )
    (net (code "81") (name "unconnected-(JP3-Pad15)") (class "Default")
      (node (ref "JP3") (pin "15") (pinfunction "15_15") (pintype "passive"))
    )
    (net (code "82") (name "unconnected-(JP3-Pad16)") (class "Default")
      (node (ref "JP3") (pin "16") (pinfunction "16_16") (pintype "passive"))
    )
    (net (code "83") (name "unconnected-(JP3-Pad17)") (class "Default")
      (node (ref "JP3") (pin "17") (pinfunction "17_17") (pintype "passive"))
    )
    (net (code "84") (name "unconnected-(JP3-Pad18)") (class "Default")
      (node (ref "JP3") (pin "18") (pinfunction "18_18") (pintype "passive"))
    )
    (net (code "85") (name "unconnected-(JP3-Pad19)") (class "Default")
      (node (ref "JP3") (pin "19") (pinfunction "19_19") (pintype "passive"))
    )
    (net (code "86") (name "unconnected-(JP3-Pad21)") (class "Default")
      (node (ref "JP3") (pin "21") (pinfunction "21_21") (pintype "passive"))
    )
    (net (code "87") (name "unconnected-(JP3-Pad22)") (class "Default")
      (node (ref "JP3") (pin "22") (pinfunction "22_22") (pintype "passive"))
    )
    (net (code "88") (name "unconnected-(JP3-Pad23)") (class "Default")
      (node (ref "JP3") (pin "23") (pinfunction "23_23") (pintype "passive"))
    )
    (net (code "89") (name "unconnected-(JP3-Pad24)") (class "Default")
      (node (ref "JP3") (pin "24") (pinfunction "24_24") (pintype "passive"))
    )
    (net (code "90") (name "unconnected-(JP3-Pad26)") (class "Default")
      (node (ref "JP3") (pin "26") (pinfunction "26_26") (pintype "passive"))
    )
    (net (code "91") (name "unconnected-(JP3-Pad27)") (class "Default")
      (node (ref "JP3") (pin "27") (pinfunction "27_27") (pintype "passive"))
    )
    (net (code "92") (name "unconnected-(JP3-Pad28)") (class "Default")
      (node (ref "JP3") (pin "28") (pinfunction "28_28") (pintype "passive"))
    )
    (net (code "93") (name "unconnected-(JP3-Pad29)") (class "Default")
      (node (ref "JP3") (pin "29") (pinfunction "29_29") (pintype "passive"))
    )
    (net (code "94") (name "unconnected-(JP3-Pad31)") (class "Default")
      (node (ref "JP3") (pin "31") (pinfunction "31_31") (pintype "passive"))
    )
    (net (code "95") (name "unconnected-(JP3-Pad32)") (class "Default")
      (node (ref "JP3") (pin "32") (pinfunction "32_32") (pintype "passive"))
    )
    (net (code "96") (name "unconnected-(JP3-Pad33)") (class "Default")
      (node (ref "JP3") (pin "33") (pinfunction "33_33") (pintype "passive"))
    )
    (net (code "97") (name "unconnected-(JP3-Pad35)") (class "Default")
      (node (ref "JP3") (pin "35") (pinfunction "35_35") (pintype "passive"))
    )
    (net (code "98") (name "unconnected-(JP3-Pad36)") (class "Default")
      (node (ref "JP3") (pin "36") (pinfunction "36_36") (pintype "passive"))
    )
    (net (code "99") (name "unconnected-(JP3-Pad37)") (class "Default")
      (node (ref "JP3") (pin "37") (pinfunction "37_37") (pintype "passive"))
    )
    (net (code "100") (name "unconnected-(JP3-Pad38)") (class "Default")
      (node (ref "JP3") (pin "38") (pinfunction "38_38") (pintype "passive"))
    )
    (net (code "101") (name "unconnected-(JP3-Pad40)") (class "Default")
      (node (ref "JP3") (pin "40") (pinfunction "40_40") (pintype "passive"))
    )
  )
)
